# MC_Isolation_Schematic.net
KiCad netlist of a schematic drawn in Altium Designer
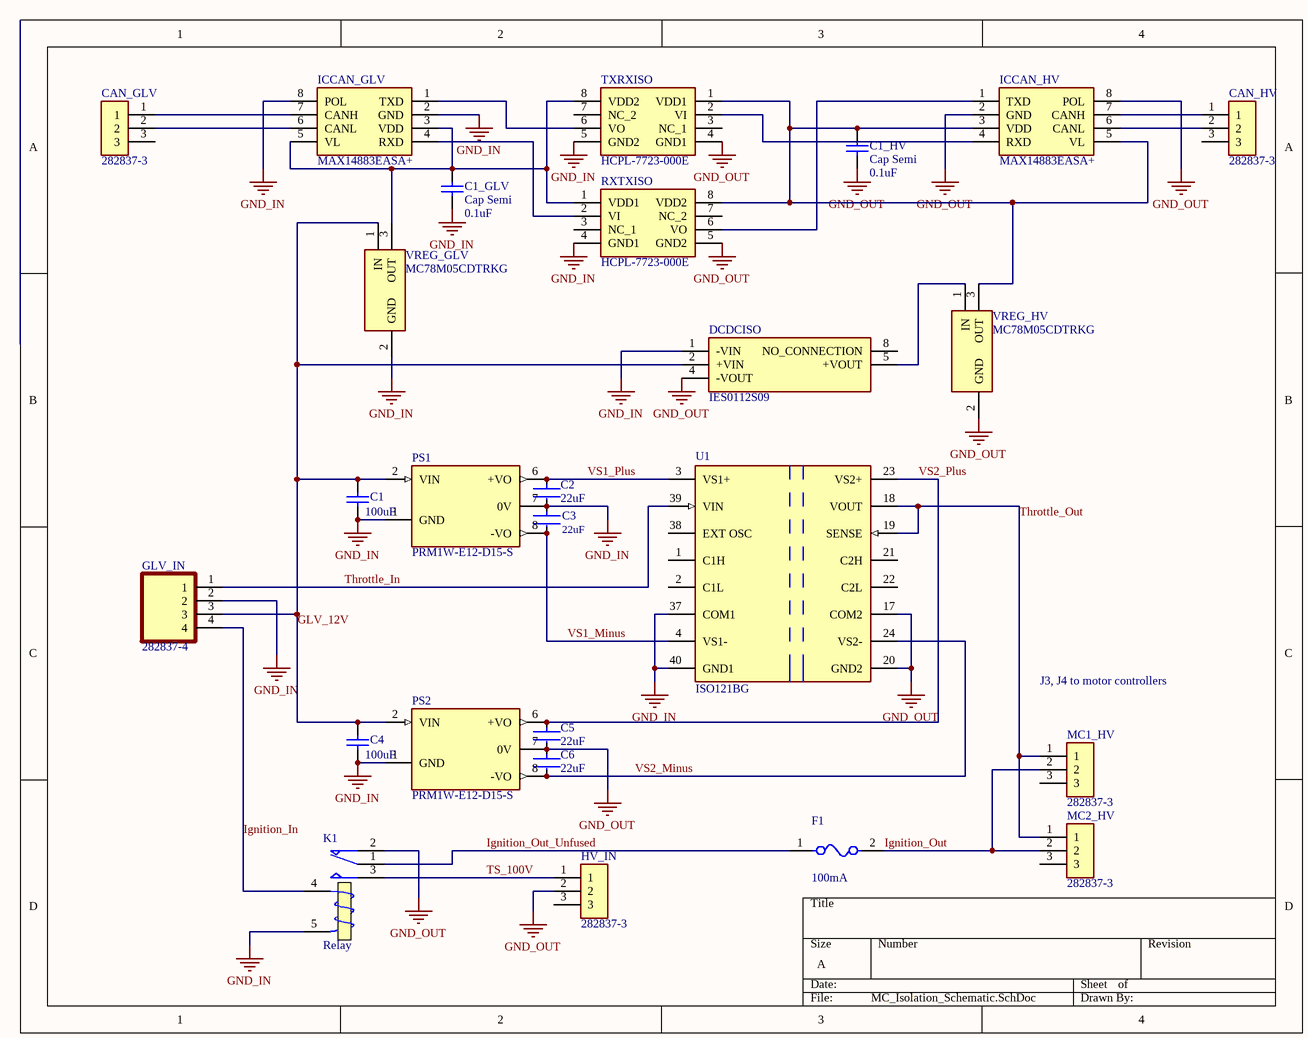
[diagram p0: MC_Isolation_Schematic.SchDoc]

(export (version "E")
  (design (tool "Eeschema 10.0.6"))
  (components
    (comp (ref "C1")
      (value "100uF")
      (footprint "RAD-0.2")
      (description "Capacitor")
      (fields (field (name "PUBLISHER") "Altium Limited"))
      (libsource (lib "Miscellaneous Devices") (part "Cap"))
    )
    (comp (ref "C1_GLV")
      (value "Cap Semi")
      (footprint "C1206")
      (description "Capacitor (Semiconductor SIM Model)")
      (fields (field (name "ALTIUM_VALUE") "0.1uF") (field (name "PUBLISHER") "Altium Limited"))
      (libsource (lib "Miscellaneous Devices") (part "Cap Semi"))
    )
    (comp (ref "C1_HV")
      (value "Cap Semi")
      (footprint "C1206")
      (description "Capacitor (Semiconductor SIM Model)")
      (fields (field (name "ALTIUM_VALUE") "0.1uF") (field (name "PUBLISHER") "Altium Limited"))
      (libsource (lib "Miscellaneous Devices") (part "Cap Semi"))
    )
    (comp (ref "C2")
      (value "22uF")
      (footprint "FP-C3216-160-0_2-IPC_B")
      (description "Multilayer Ceramic Capacitors 1uF ±10% 50V X7R SMD 1206")
      (fields (field (name "VOLTAGE") "25V") (field (name "TOLERANCE") "10%"))
      (libsource (lib "Altium Content Vault") (part "11868f565c42a9108669ba33697ecf6"))
    )
    (comp (ref "C3")
      (value "22uF")
      (footprint "FP-C3216-160-0_2-IPC_B")
      (description "Multilayer Ceramic Capacitors 1uF ±10% 50V X7R SMD 1206")
      (fields (field (name "VOLTAGE") "25V") (field (name "TOLERANCE") "10%"))
      (libsource (lib "Altium Content Vault") (part "11868f565c42a9108669ba33697ecf6"))
    )
    (comp (ref "C4")
      (value "100uF")
      (footprint "RAD-0.2")
      (description "Capacitor")
      (fields (field (name "PUBLISHER") "Altium Limited"))
      (libsource (lib "Miscellaneous Devices") (part "Cap"))
    )
    (comp (ref "C5")
      (value "22uF")
      (footprint "FP-C3216-160-0_2-IPC_B")
      (description "Multilayer Ceramic Capacitors 1uF ±10% 50V X7R SMD 1206")
      (fields (field (name "VOLTAGE") "25V") (field (name "TOLERANCE") "10%"))
      (libsource (lib "Altium Content Vault") (part "11868f565c42a9108669ba33697ecf6"))
    )
    (comp (ref "C6")
      (value "22uF")
      (footprint "FP-C3216-160-0_2-IPC_B")
      (description "Multilayer Ceramic Capacitors 1uF ±10% 50V X7R SMD 1206")
      (fields (field (name "VOLTAGE") "25V") (field (name "TOLERANCE") "10%"))
      (libsource (lib "Altium Content Vault") (part "11868f565c42a9108669ba33697ecf6"))
    )
    (comp (ref "CAN_GLV")
      (value "282837-3")
      (footprint "TE_282837-3:TE_282837-3")
      (description "Wire to Board 3 Position 5.08 mm Pitch 30-16 AWG Euro Style Terminal Block")
      (fields (field (name "MF") "TE Connectivity"))
      (libsource (lib "") (part "282837-3_1"))
    )
    (comp (ref "CAN_HV")
      (value "282837-3")
      (footprint "TE_282837-3:TE_282837-3")
      (description "Wire to Board 3 Position 5.08 mm Pitch 30-16 AWG Euro Style Terminal Block")
      (fields (field (name "MF") "TE Connectivity"))
      (libsource (lib "282837-3") (part "282837-3"))
    )
    (comp (ref "DCDCISO")
      (value "IES0112S09")
      (footprint "SamacSys:IES0105S05H")
      (description "Power Supply")
      (fields
        (field (name "MANUFACTURER_PART_NUMBER") "IES0105S03")
        (field (name "MOUSER PART NUMBER") "209-IES0105S03")
      )
      (libsource (lib "*") (part "IES0105S03"))
    )
    (comp (ref "F1")
      (value "100mA")
      (footprint "FP-0154-MFG")
      (description "FUSE BOARD MNT 100MA 125VAC/VDC")
      (fields
        (field (name "OCTOPART") "https://octopart.com/0154.100dr-littelfuse-557956")
        (field (name "MANUFACTURER") "Littelfuse Inc")
      )
      (libsource (lib "Altium Content Vault") (part "5bcf9b9f640e542cf0359d10258e979"))
    )
    (comp (ref "GLV_IN")
      (value "282837-4")
      (footprint "TE_282837-4:TE_282837-4")
      (description "4 Position Wire to Board Terminal Block Horizontal with Board 0.200 (5.08mm)")
      (fields (field (name "MF") "TE Connectivity"))
      (libsource (lib "282837-4") (part "282837-4"))
    )
    (comp (ref "HV_IN")
      (value "282837-3")
      (footprint "TE_282837-3:TE_282837-3")
      (description "Wire to Board 3 Position 5.08 mm Pitch 30-16 AWG Euro Style Terminal Block")
      (fields (field (name "MF") "TE Connectivity"))
      (libsource (lib "282837-3") (part "282837-3"))
    )
    (comp (ref "ICCAN_GLV")
      (value "MAX14883EASA+")
      (footprint "SamacSys:SOIC127P600X175-8N")
      (description "Integrated Circuit")
      (fields (field (name "MOUSER PART NUMBER") "700-MAX14883EASA+"))
      (libsource (lib "*") (part "MAX14883EASA+"))
    )
    (comp (ref "ICCAN_HV")
      (value "MAX14883EASA+")
      (footprint "SamacSys:SOIC127P600X175-8N")
      (description "Integrated Circuit")
      (fields (field (name "MOUSER PART NUMBER") "700-MAX14883EASA+"))
      (libsource (lib "") (part "MAX14883EASA+_1"))
    )
    (comp (ref "K1")
      (value "Relay")
      (footprint "my2-02-UnalmisAtwood:PCBComponent_1")
      (description "SPDT Relay")
      (fields (field (name "PUBLISHER") "Altium Limited"))
      (libsource (lib "Miscellaneous Devices") (part "Relay"))
    )
    (comp (ref "MC1_HV")
      (value "282837-3")
      (footprint "TE_282837-3:TE_282837-3")
      (description "Wire to Board 3 Position 5.08 mm Pitch 30-16 AWG Euro Style Terminal Block")
      (fields (field (name "MF") "TE Connectivity"))
      (libsource (lib "282837-3") (part "282837-3"))
    )
    (comp (ref "MC2_HV")
      (value "282837-3")
      (footprint "TE_282837-3:TE_282837-3")
      (description "Wire to Board 3 Position 5.08 mm Pitch 30-16 AWG Euro Style Terminal Block")
      (fields (field (name "MF") "TE Connectivity"))
      (libsource (lib "282837-3") (part "282837-3"))
    )
    (comp (ref "PS1")
      (value "PRM1W-E12-D15-S")
      (footprint "CONV_PRM1W-E12-D15-S")
      (description "1 W, 8:1 Input Range, Single/Dual Regulated Output, 8 Pin SIP, 3000 Vdc Isolation, Dc-Dc Converter")
      (fields (field (name "MF") "{'manufacturer': u'CUI'}"))
      (libsource (lib "PRM1W-E12-D15-S") (part "PRM1W-E12-D15-S"))
    )
    (comp (ref "PS2")
      (value "PRM1W-E12-D15-S")
      (footprint "CONV_PRM1W-E12-D15-S")
      (description "1 W, 8:1 Input Range, Single/Dual Regulated Output, 8 Pin SIP, 3000 Vdc Isolation, Dc-Dc Converter")
      (fields (field (name "MF") "{'manufacturer': u'CUI'}"))
      (libsource (lib "PRM1W-E12-D15-S") (part "PRM1W-E12-D15-S"))
    )
    (comp (ref "RXTXISO")
      (value "HCPL-7723-000E")
      (footprint "SamacSys:DIP762W65P254L965H470Q8N")
      (description "Integrated Circuit")
      (fields (field (name "MOUSER PART NUMBER") "630-HCPL-7723-000E"))
      (libsource (lib "*") (part "HCPL-7723-000E"))
    )
    (comp (ref "TXRXISO")
      (value "HCPL-7723-000E")
      (footprint "SamacSys:DIP762W65P254L965H470Q8N")
      (description "Integrated Circuit")
      (fields (field (name "MOUSER PART NUMBER") "630-HCPL-7723-000E"))
      (libsource (lib "") (part "HCPL-7723-000E_1"))
    )
    (comp (ref "U1")
      (value "ISO121BG")
      (footprint "FP-JVD0016A-MFG")
      (description "IC OPAMP ISOLATION 1 CIRC 16CDIP")
      (libsource (lib "Altium Content Vault") (part "aa3543eb15e901695e3e813befe1bad"))
    )
    (comp (ref "VREG_GLV")
      (value "MC78M05CDTRKG")
      (footprint "SamacSys:LM317MADTRKG")
      (description "Integrated Circuit")
      (fields (field (name "MOUSER PART NUMBER") "863-MC78M05CDTRKG"))
      (libsource (lib "*") (part "MC78M05CDTRKG"))
    )
    (comp (ref "VREG_HV")
      (value "MC78M05CDTRKG")
      (footprint "SamacSys:LM317MADTRKG")
      (description "Integrated Circuit")
      (fields (field (name "MOUSER PART NUMBER") "863-MC78M05CDTRKG"))
      (libsource (lib "*") (part "MC78M05CDTRKG"))
    )
  )
  (nets
    (net (code "1") (name "/GLV_12V") (class "Default")
      (node (ref "C1") (pin "2") (pinfunction "2_2") (pintype "passive"))
      (node (ref "C4") (pin "2") (pinfunction "2_2") (pintype "passive"))
      (node (ref "DCDCISO") (pin "2") (pinfunction "+VIN_2") (pintype "passive"))
      (node (ref "GLV_IN") (pin "3") (pinfunction "3_3") (pintype "passive"))
      (node (ref "PS1") (pin "2") (pinfunction "VIN_2") (pintype "input"))
      (node (ref "PS2") (pin "2") (pinfunction "VIN_2") (pintype "input"))
      (node (ref "VREG_GLV") (pin "1") (pinfunction "IN_1") (pintype "passive"))
    )
    (net (code "2") (name "/Ignition_In") (class "Default")
      (node (ref "GLV_IN") (pin "4") (pinfunction "4_4") (pintype "passive"))
      (node (ref "K1") (pin "4") (pinfunction "T1_4") (pintype "passive"))
    )
    (net (code "3") (name "/Ignition_Out") (class "Default")
      (node (ref "F1") (pin "2") (pinfunction "2_2") (pintype "passive"))
      (node (ref "MC1_HV") (pin "2") (pinfunction "2_2") (pintype "passive"))
      (node (ref "MC2_HV") (pin "2") (pinfunction "2_2") (pintype "passive"))
    )
    (net (code "4") (name "/Ignition_Out_Unfused") (class "Default")
      (node (ref "F1") (pin "1") (pinfunction "1_1") (pintype "passive"))
      (node (ref "K1") (pin "1") (pinfunction "COM_1") (pintype "passive"))
    )
    (net (code "5") (name "/TS_100V") (class "Default")
      (node (ref "HV_IN") (pin "1") (pinfunction "1_1") (pintype "passive"))
      (node (ref "K1") (pin "3") (pinfunction "NO_3") (pintype "passive"))
    )
    (net (code "6") (name "/Throttle_In") (class "Default")
      (node (ref "GLV_IN") (pin "1") (pinfunction "1_1") (pintype "passive"))
      (node (ref "U1") (pin "39") (pinfunction "VIN_39") (pintype "input"))
    )
    (net (code "7") (name "/Throttle_Out") (class "Default")
      (node (ref "MC1_HV") (pin "1") (pinfunction "1_1") (pintype "passive"))
      (node (ref "MC2_HV") (pin "1") (pinfunction "1_1") (pintype "passive"))
      (node (ref "U1") (pin "18") (pinfunction "VOUT_18") (pintype "power_in"))
      (node (ref "U1") (pin "19") (pinfunction "SENSE_19") (pintype "input"))
    )
    (net (code "8") (name "/VS1_Minus") (class "Default")
      (node (ref "C3") (pin "2") (pinfunction "2_2") (pintype "passive"))
      (node (ref "PS1") (pin "8") (pinfunction "-VO_8") (pintype "output"))
      (node (ref "U1") (pin "4") (pinfunction "VS1-_4") (pintype "power_in"))
    )
    (net (code "9") (name "/VS1_Plus") (class "Default")
      (node (ref "C2") (pin "1") (pinfunction "1_1") (pintype "passive"))
      (node (ref "PS1") (pin "6") (pinfunction "+VO_6") (pintype "output"))
      (node (ref "U1") (pin "3") (pinfunction "VS1+_3") (pintype "power_in"))
    )
    (net (code "10") (name "/VS2_Minus") (class "Default")
      (node (ref "C6") (pin "2") (pinfunction "2_2") (pintype "passive"))
      (node (ref "PS2") (pin "8") (pinfunction "-VO_8") (pintype "output"))
      (node (ref "U1") (pin "24") (pinfunction "VS2-_24") (pintype "power_in"))
    )
    (net (code "11") (name "/VS2_Plus") (class "Default")
      (node (ref "C5") (pin "1") (pinfunction "1_1") (pintype "passive"))
      (node (ref "PS2") (pin "6") (pinfunction "+VO_6") (pintype "output"))
      (node (ref "U1") (pin "23") (pinfunction "VS2+_23") (pintype "power_in"))
    )
    (net (code "12") (name "GND_IN") (class "Default")
      (node (ref "C1") (pin "1") (pinfunction "1_1") (pintype "passive"))
      (node (ref "C1_GLV") (pin "1") (pinfunction "1_1") (pintype "passive"))
      (node (ref "C2") (pin "2") (pinfunction "2_2") (pintype "passive"))
      (node (ref "C3") (pin "1") (pinfunction "1_1") (pintype "passive"))
      (node (ref "C4") (pin "1") (pinfunction "1_1") (pintype "passive"))
      (node (ref "DCDCISO") (pin "1") (pinfunction "-VIN_1") (pintype "passive"))
      (node (ref "GLV_IN") (pin "2") (pinfunction "2_2") (pintype "passive"))
      (node (ref "ICCAN_GLV") (pin "2") (pinfunction "GND_2") (pintype "passive"))
      (node (ref "ICCAN_GLV") (pin "8") (pinfunction "POL_8") (pintype "passive"))
      (node (ref "K1") (pin "5") (pinfunction "T2_5") (pintype "passive"))
      (node (ref "PS1") (pin "1") (pinfunction "GND_1") (pintype "power_in"))
      (node (ref "PS1") (pin "7") (pinfunction "0V_7") (pintype "passive"))
      (node (ref "PS2") (pin "1") (pinfunction "GND_1") (pintype "power_in"))
      (node (ref "RXTXISO") (pin "4") (pinfunction "GND1_4") (pintype "passive"))
      (node (ref "TXRXISO") (pin "5") (pinfunction "GND2_5") (pintype "passive"))
      (node (ref "U1") (pin "37") (pinfunction "COM1_37") (pintype "passive"))
      (node (ref "U1") (pin "40") (pinfunction "GND1_40") (pintype "power_in"))
      (node (ref "VREG_GLV") (pin "2") (pinfunction "GND_2") (pintype "passive"))
    )
    (net (code "13") (name "GND_OUT") (class "Default")
      (node (ref "C1_HV") (pin "1") (pinfunction "1_1") (pintype "passive"))
      (node (ref "C5") (pin "2") (pinfunction "2_2") (pintype "passive"))
      (node (ref "C6") (pin "1") (pinfunction "1_1") (pintype "passive"))
      (node (ref "DCDCISO") (pin "4") (pinfunction "-VOUT_4") (pintype "passive"))
      (node (ref "HV_IN") (pin "2") (pinfunction "2_2") (pintype "passive"))
      (node (ref "ICCAN_HV") (pin "2") (pinfunction "GND_2") (pintype "passive"))
      (node (ref "ICCAN_HV") (pin "8") (pinfunction "POL_8") (pintype "passive"))
      (node (ref "K1") (pin "2") (pinfunction "NC_2") (pintype "passive"))
      (node (ref "PS2") (pin "7") (pinfunction "0V_7") (pintype "passive"))
      (node (ref "RXTXISO") (pin "5") (pinfunction "GND2_5") (pintype "passive"))
      (node (ref "TXRXISO") (pin "4") (pinfunction "GND1_4") (pintype "passive"))
      (node (ref "U1") (pin "17") (pinfunction "COM2_17") (pintype "passive"))
      (node (ref "U1") (pin "20") (pinfunction "GND2_20") (pintype "power_in"))
      (node (ref "VREG_HV") (pin "2") (pinfunction "GND_2") (pintype "passive"))
    )
    (net (code "14") (name "Net-(DCDCISO-+VOUT)") (class "Default")
      (node (ref "DCDCISO") (pin "5") (pinfunction "+VOUT_5") (pintype "passive"))
      (node (ref "VREG_HV") (pin "1") (pinfunction "IN_1") (pintype "passive"))
    )
    (net (code "15") (name "Net-(ICCAN_GLV-CANH)") (class "Default")
      (node (ref "CAN_GLV") (pin "1") (pinfunction "1_1") (pintype "passive"))
      (node (ref "ICCAN_GLV") (pin "7") (pinfunction "CANH_7") (pintype "passive"))
    )
    (net (code "16") (name "Net-(ICCAN_GLV-CANL)") (class "Default")
      (node (ref "CAN_GLV") (pin "2") (pinfunction "2_2") (pintype "passive"))
      (node (ref "ICCAN_GLV") (pin "6") (pinfunction "CANL_6") (pintype "passive"))
    )
    (net (code "17") (name "Net-(ICCAN_GLV-RXD)") (class "Default")
      (node (ref "ICCAN_GLV") (pin "4") (pinfunction "RXD_4") (pintype "passive"))
      (node (ref "RXTXISO") (pin "2") (pinfunction "VI_2") (pintype "passive"))
    )
    (net (code "18") (name "Net-(ICCAN_GLV-TXD)") (class "Default")
      (node (ref "ICCAN_GLV") (pin "1") (pinfunction "TXD_1") (pintype "passive"))
      (node (ref "TXRXISO") (pin "6") (pinfunction "VO_6") (pintype "passive"))
    )
    (net (code "19") (name "Net-(ICCAN_GLV-VDD)") (class "Default")
      (node (ref "C1_GLV") (pin "2") (pinfunction "2_2") (pintype "passive"))
      (node (ref "ICCAN_GLV") (pin "3") (pinfunction "VDD_3") (pintype "passive"))
      (node (ref "ICCAN_GLV") (pin "5") (pinfunction "VL_5") (pintype "passive"))
      (node (ref "RXTXISO") (pin "1") (pinfunction "VDD1_1") (pintype "passive"))
      (node (ref "TXRXISO") (pin "8") (pinfunction "VDD2_8") (pintype "passive"))
      (node (ref "VREG_GLV") (pin "3") (pinfunction "OUT_3") (pintype "passive"))
    )
    (net (code "20") (name "Net-(ICCAN_HV-CANH)") (class "Default")
      (node (ref "CAN_HV") (pin "1") (pinfunction "1_1") (pintype "passive"))
      (node (ref "ICCAN_HV") (pin "7") (pinfunction "CANH_7") (pintype "passive"))
    )
    (net (code "21") (name "Net-(ICCAN_HV-CANL)") (class "Default")
      (node (ref "CAN_HV") (pin "2") (pinfunction "2_2") (pintype "passive"))
      (node (ref "ICCAN_HV") (pin "6") (pinfunction "CANL_6") (pintype "passive"))
    )
    (net (code "22") (name "Net-(ICCAN_HV-RXD)") (class "Default")
      (node (ref "ICCAN_HV") (pin "4") (pinfunction "RXD_4") (pintype "passive"))
      (node (ref "TXRXISO") (pin "2") (pinfunction "VI_2") (pintype "passive"))
    )
    (net (code "23") (name "Net-(ICCAN_HV-TXD)") (class "Default")
      (node (ref "ICCAN_HV") (pin "1") (pinfunction "TXD_1") (pintype "passive"))
      (node (ref "RXTXISO") (pin "6") (pinfunction "VO_6") (pintype "passive"))
    )
    (net (code "24") (name "Net-(ICCAN_HV-VDD)") (class "Default")
      (node (ref "C1_HV") (pin "2") (pinfunction "2_2") (pintype "passive"))
      (node (ref "ICCAN_HV") (pin "3") (pinfunction "VDD_3") (pintype "passive"))
      (node (ref "ICCAN_HV") (pin "5") (pinfunction "VL_5") (pintype "passive"))
      (node (ref "RXTXISO") (pin "8") (pinfunction "VDD2_8") (pintype "passive"))
      (node (ref "TXRXISO") (pin "1") (pinfunction "VDD1_1") (pintype "passive"))
      (node (ref "VREG_HV") (pin "3") (pinfunction "OUT_3") (pintype "passive"))
    )
    (net (code "25") (name "unconnected-(CAN_GLV-Pad3)") (class "Default")
      (node (ref "CAN_GLV") (pin "3") (pinfunction "3_3") (pintype "passive"))
    )
    (net (code "26") (name "unconnected-(CAN_HV-Pad3)") (class "Default")
      (node (ref "CAN_HV") (pin "3") (pinfunction "3_3") (pintype "passive"))
    )
    (net (code "27") (name "unconnected-(DCDCISO-NO_CONNECTION-Pad8)") (class "Default")
      (node (ref "DCDCISO") (pin "8") (pinfunction "NO_CONNECTION_8") (pintype "passive"))
    )
    (net (code "28") (name "unconnected-(HV_IN-Pad3)") (class "Default")
      (node (ref "HV_IN") (pin "3") (pinfunction "3_3") (pintype "passive"))
    )
    (net (code "29") (name "unconnected-(MC1_HV-Pad3)") (class "Default")
      (node (ref "MC1_HV") (pin "3") (pinfunction "3_3") (pintype "passive"))
    )
    (net (code "30") (name "unconnected-(MC2_HV-Pad3)") (class "Default")
      (node (ref "MC2_HV") (pin "3") (pinfunction "3_3") (pintype "passive"))
    )
    (net (code "31") (name "unconnected-(RXTXISO-NC_1-Pad3)") (class "Default")
      (node (ref "RXTXISO") (pin "3") (pinfunction "NC_1_3") (pintype "passive"))
    )
    (net (code "32") (name "unconnected-(RXTXISO-NC_2-Pad7)") (class "Default")
      (node (ref "RXTXISO") (pin "7") (pinfunction "NC_2_7") (pintype "passive"))
    )
    (net (code "33") (name "unconnected-(TXRXISO-NC_1-Pad3)") (class "Default")
      (node (ref "TXRXISO") (pin "3") (pinfunction "NC_1_3") (pintype "passive"))
    )
    (net (code "34") (name "unconnected-(TXRXISO-NC_2-Pad7)") (class "Default")
      (node (ref "TXRXISO") (pin "7") (pinfunction "NC_2_7") (pintype "passive"))
    )
    (net (code "35") (name "unconnected-(U1-C1H-Pad1)") (class "Default")
      (node (ref "U1") (pin "1") (pinfunction "C1H_1") (pintype "passive"))
    )
    (net (code "36") (name "unconnected-(U1-C1L-Pad2)") (class "Default")
      (node (ref "U1") (pin "2") (pinfunction "C1L_2") (pintype "passive"))
    )
    (net (code "37") (name "unconnected-(U1-C2H-Pad21)") (class "Default")
      (node (ref "U1") (pin "21") (pinfunction "C2H_21") (pintype "passive"))
    )
    (net (code "38") (name "unconnected-(U1-C2L-Pad22)") (class "Default")
      (node (ref "U1") (pin "22") (pinfunction "C2L_22") (pintype "passive"))
    )
    (net (code "39") (name "unconnected-(U1-EXT_OSC-Pad38)") (class "Default")
      (node (ref "U1") (pin "38") (pinfunction "EXT_OSC_38") (pintype "passive"))
    )
  )
)
